# regulators.net
KiCad netlist of a schematic drawn in Altium Designer
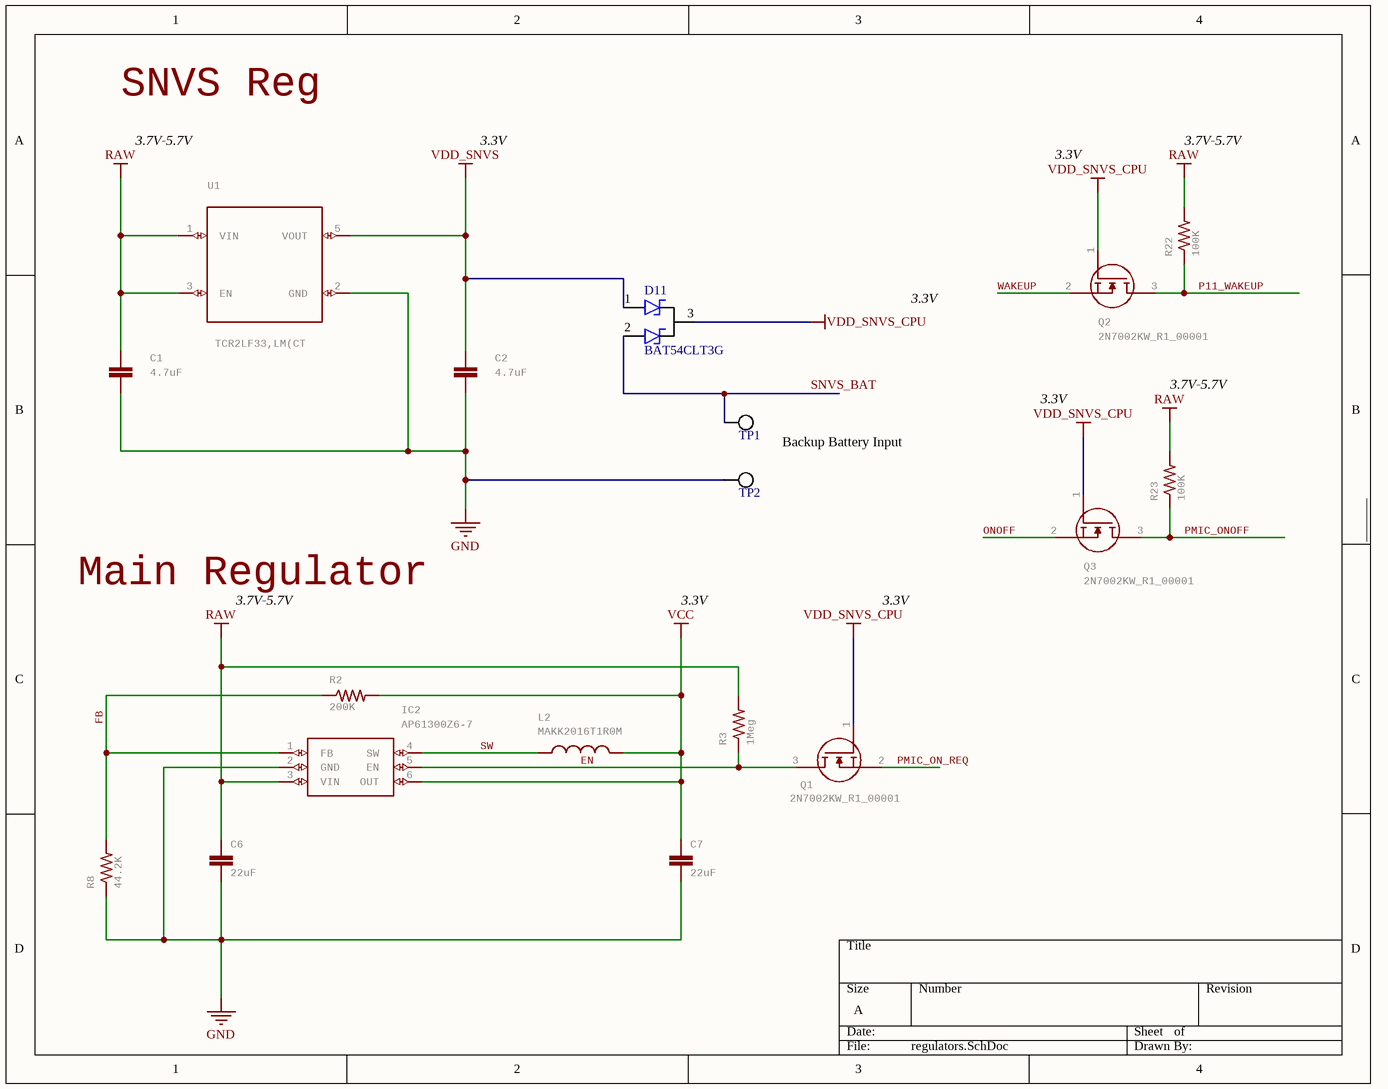
[diagram p0: regulators.SchDoc]

(export (version "E")
  (design (tool "Eeschema 10.0.6"))
  (components
    (comp (ref "C1")
      (value "4.7uF")
      (footprint "0402-CAP")
      (description "CapacitorStandard 0603 ceramic capacitor, and 0.1\" leaded capacitor.")
      (fields (field (name "MPN") "JMK105BBJ475MV-F"))
      (libsource (lib "rt10") (part "CAP0402-CAP"))
    )
    (comp (ref "C2")
      (value "4.7uF")
      (footprint "0402-CAP")
      (description "CapacitorStandard 0603 ceramic capacitor, and 0.1\" leaded capacitor.")
      (fields (field (name "MPN") "JMK105BBJ475MV-F"))
      (libsource (lib "rt10") (part "CAP0402-CAP"))
    )
    (comp (ref "C6")
      (value "22uF")
      (footprint "0805")
      (fields (field (name "MPN") "CL21A226MQQNNNE"))
      (libsource (lib "rt10") (part "22UF-0805-6.3V-20%"))
    )
    (comp (ref "C7")
      (value "22uF")
      (footprint "0805")
      (fields (field (name "MPN") "CL21A226MQQNNNE"))
      (libsource (lib "rt10") (part "22UF-0805-6.3V-20%"))
    )
    (comp (ref "D11")
      (value "Dual Schottky")
      (footprint "SOT-23-3")
      (fields (field (name "MPN") "BAT54CLT3G") (field (name "PART NUMBER") "BAT54CLT3G"))
      (libsource (lib "rt10") (part "Dual Schottky"))
    )
    (comp (ref "IC2")
      (value "AP61300Z6-7")
      (footprint "SOTFL50P162X60-6N")
      (description "DCDC Conv LV Buck SOT563 T&R 3K   Source:  Datasheet")
      (fields (field (name "MOUSER_PART_NUMBER") "621-AP61300Z6-7"))
      (libsource (lib "rt10") (part "AP61300Z6-7"))
    )
    (comp (ref "L2")
      (value "MAKK2016T1R0M")
      (footprint "INDC2016X100N")
      (description "Ind Power Wirewound 1uH 20% 2MHz Metal 2200mA 0806 Check availability")
      (fields (field (name "MF") "Taiyo Yuden"))
      (libsource (lib "rt10") (part "MAKK2016T1R0M"))
    )
    (comp (ref "Q1")
      (value "2N7002KW_R1_00001")
      (footprint "SOT65P210X110-3N")
      (description "MOSFET 60V N-Channel Enhancement Mode MOSFET - ESD Protected   Source:  Datasheet")
      (fields (field (name "MOUSER_PART_NUMBER") "241-2N7002KWR100001"))
      (libsource (lib "rt10") (part "2N7002KW_R1_00001"))
    )
    (comp (ref "Q2")
      (value "2N7002KW_R1_00001")
      (footprint "SOT65P210X110-3N")
      (description "MOSFET 60V N-Channel Enhancement Mode MOSFET - ESD Protected   Source:  Datasheet")
      (fields (field (name "MOUSER_PART_NUMBER") "241-2N7002KWR100001"))
      (libsource (lib "rt10") (part "2N7002KW_R1_00001"))
    )
    (comp (ref "Q3")
      (value "2N7002KW_R1_00001")
      (footprint "SOT65P210X110-3N")
      (description "MOSFET 60V N-Channel Enhancement Mode MOSFET - ESD Protected   Source:  Datasheet")
      (fields (field (name "MOUSER_PART_NUMBER") "241-2N7002KWR100001"))
      (libsource (lib "rt10") (part "2N7002KW_R1_00001"))
    )
    (comp (ref "R2")
      (value "200K")
      (footprint "0402-RES")
      (description "ResistorBasic schematic elements and footprints for 0603, 1206, and PTH resistors.")
      (fields (field (name "MPN") "CRCW0402200KFKEDC"))
      (libsource (lib "rt10") (part "RESISTOR0402-RES"))
    )
    (comp (ref "R3")
      (value "1Meg")
      (footprint "0402-RES")
      (description "ResistorBasic schematic elements and footprints for 0603, 1206, and PTH resistors.")
      (fields (field (name "MPN") "CRCW04021M00FKEDC"))
      (libsource (lib "rt10") (part "RESISTOR0402-RES"))
    )
    (comp (ref "R8")
      (value "44.2K")
      (footprint "0402-RES")
      (description "ResistorBasic schematic elements and footprints for 0603, 1206, and PTH resistors.")
      (fields (field (name "MPN") "AC0402FR-0744K2L"))
      (libsource (lib "rt10") (part "RESISTOR0402-RES"))
    )
    (comp (ref "R22")
      (value "100K")
      (footprint "0402-RES")
      (description "ResistorBasic schematic elements and footprints for 0603, 1206, and PTH resistors.")
      (fields (field (name "MPN") "AC0402FR-07100KL"))
      (libsource (lib "rt10") (part "RESISTOR0402-RES"))
    )
    (comp (ref "R23")
      (value "100K")
      (footprint "0402-RES")
      (description "ResistorBasic schematic elements and footprints for 0603, 1206, and PTH resistors.")
      (fields (field (name "MPN") "AC0402FR-07100KL"))
      (libsource (lib "rt10") (part "RESISTOR0402-RES"))
    )
    (comp (ref "TP1") (value "TP") (footprint "TP_1p8") (libsource (lib "rt10") (part "TP")))
    (comp (ref "TP2") (value "TP") (footprint "TP_1p8") (libsource (lib "rt10") (part "TP")))
    (comp (ref "U1")
      (value "TCR2LF33,LM(CT")
      (footprint "SOT-23-5")
      (libsource (lib "rt10") (part "TCR2LF33,LM(CT"))
    )
  )
  (nets
    (net (code "1") (name "/EN") (class "Default")
      (node (ref "IC2") (pin "5") (pinfunction "EN_5") (pintype "bidirectional"))
      (node (ref "Q1") (pin "3") (pinfunction "D_3") (pintype "bidirectional"))
      (node (ref "R3") (pin "1") (pinfunction "1_1") (pintype "passive"))
    )
    (net (code "2") (name "/FB") (class "Default")
      (node (ref "IC2") (pin "1") (pinfunction "FB_1") (pintype "bidirectional"))
      (node (ref "R2") (pin "1") (pinfunction "1_1") (pintype "passive"))
      (node (ref "R8") (pin "2") (pinfunction "2_2") (pintype "passive"))
    )
    (net (code "3") (name "/ONOFF") (class "Default")
      (node (ref "Q3") (pin "2") (pinfunction "S_2") (pintype "bidirectional"))
    )
    (net (code "4") (name "/P11_WAKEUP") (class "Default")
      (node (ref "Q2") (pin "3") (pinfunction "D_3") (pintype "bidirectional"))
      (node (ref "R22") (pin "1") (pinfunction "1_1") (pintype "passive"))
    )
    (net (code "5") (name "/PMIC_ONOFF") (class "Default")
      (node (ref "Q3") (pin "3") (pinfunction "D_3") (pintype "bidirectional"))
      (node (ref "R23") (pin "1") (pinfunction "1_1") (pintype "passive"))
    )
    (net (code "6") (name "/PMIC_ON_REQ") (class "Default")
      (node (ref "Q1") (pin "2") (pinfunction "S_2") (pintype "bidirectional"))
    )
    (net (code "7") (name "/SNVS_BAT") (class "Default")
      (node (ref "D11") (pin "2") (pinfunction "2_2") (pintype "passive"))
      (node (ref "TP1") (pin "1") (pinfunction "1_1") (pintype "passive"))
    )
    (net (code "8") (name "/SW") (class "Default")
      (node (ref "IC2") (pin "4") (pinfunction "SW_4") (pintype "bidirectional"))
      (node (ref "L2") (pin "1") (pinfunction "1_1") (pintype "passive"))
    )
    (net (code "9") (name "/WAKEUP") (class "Default")
      (node (ref "Q2") (pin "2") (pinfunction "S_2") (pintype "bidirectional"))
    )
    (net (code "10") (name "GND") (class "Default")
      (node (ref "C1") (pin "1") (pinfunction "1_1") (pintype "passive"))
      (node (ref "C2") (pin "1") (pinfunction "1_1") (pintype "passive"))
      (node (ref "C6") (pin "2") (pinfunction "2_2") (pintype "passive"))
      (node (ref "C7") (pin "2") (pinfunction "2_2") (pintype "passive"))
      (node (ref "IC2") (pin "2") (pinfunction "GND_2") (pintype "bidirectional"))
      (node (ref "R8") (pin "1") (pinfunction "1_1") (pintype "passive"))
      (node (ref "TP2") (pin "1") (pinfunction "1_1") (pintype "passive"))
      (node (ref "U1") (pin "2") (pinfunction "GND_2") (pintype "bidirectional"))
    )
    (net (code "11") (name "RAW") (class "Default")
      (node (ref "C1") (pin "2") (pinfunction "2_2") (pintype "passive"))
      (node (ref "C6") (pin "1") (pinfunction "1_1") (pintype "passive"))
      (node (ref "IC2") (pin "3") (pinfunction "VIN_3") (pintype "bidirectional"))
      (node (ref "R22") (pin "2") (pinfunction "2_2") (pintype "passive"))
      (node (ref "R23") (pin "2") (pinfunction "2_2") (pintype "passive"))
      (node (ref "R3") (pin "2") (pinfunction "2_2") (pintype "passive"))
      (node (ref "U1") (pin "1") (pinfunction "VIN_1") (pintype "bidirectional"))
      (node (ref "U1") (pin "3") (pinfunction "EN_3") (pintype "bidirectional"))
    )
    (net (code "12") (name "VCC") (class "Default")
      (node (ref "C7") (pin "1") (pinfunction "1_1") (pintype "passive"))
      (node (ref "IC2") (pin "6") (pinfunction "OUT_6") (pintype "bidirectional"))
      (node (ref "L2") (pin "2") (pinfunction "2_2") (pintype "passive"))
      (node (ref "R2") (pin "2") (pinfunction "2_2") (pintype "passive"))
    )
    (net (code "13") (name "VDD_SNVS") (class "Default")
      (node (ref "C2") (pin "2") (pinfunction "2_2") (pintype "passive"))
      (node (ref "D11") (pin "1") (pinfunction "1_1") (pintype "passive"))
      (node (ref "U1") (pin "5") (pinfunction "VOUT_5") (pintype "bidirectional"))
    )
    (net (code "14") (name "VDD_SNVS_CPU") (class "Default")
      (node (ref "D11") (pin "3") (pinfunction "3_3") (pintype "passive"))
      (node (ref "Q1") (pin "1") (pinfunction "G_1") (pintype "bidirectional"))
      (node (ref "Q2") (pin "1") (pinfunction "G_1") (pintype "bidirectional"))
      (node (ref "Q3") (pin "1") (pinfunction "G_1") (pintype "bidirectional"))
    )
  )
)
